# sensor.net
KiCad netlist of a schematic drawn in Altium Designer
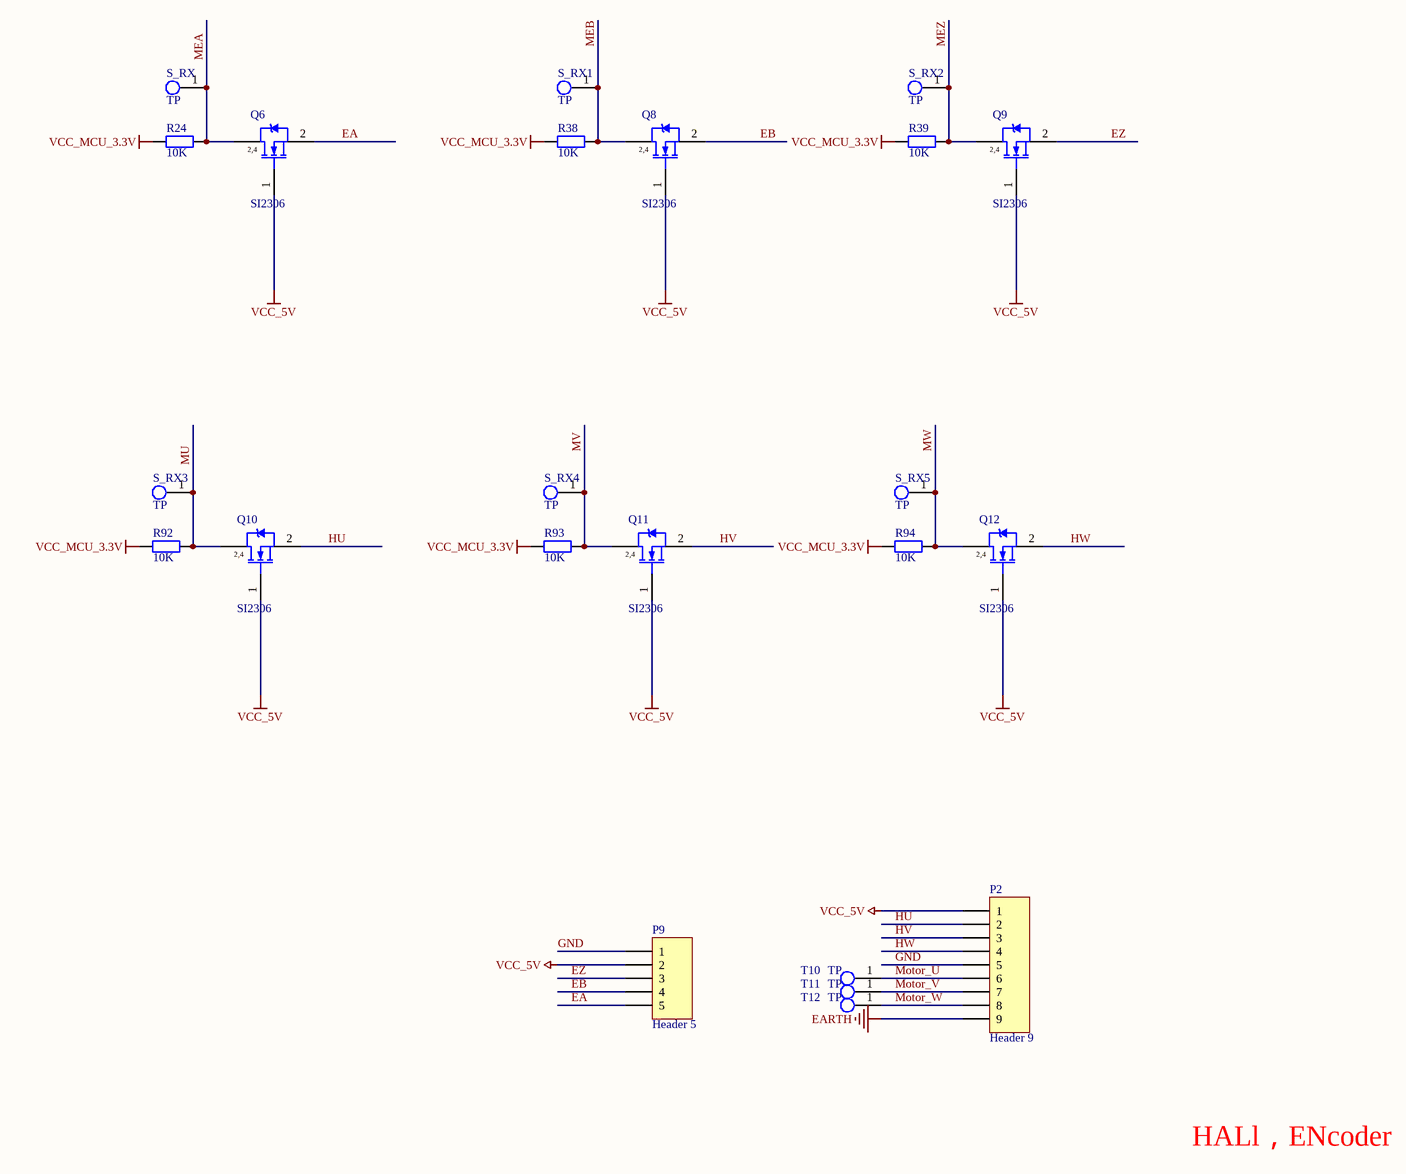
[diagram p0: sensor.SchDoc]

(export (version "E")
  (design (tool "Eeschema 10.0.6"))
  (components
    (comp (ref "P2")
      (value "Header 9")
      (footprint "XA2.5-9P")
      (description "Header, 9-Pin")
      (fields (field (name "PUBLISHER") "Altium Limited"))
      (libsource (lib "Miscellaneous Connectors") (part "Header 9"))
    )
    (comp (ref "P9")
      (value "Header 5")
      (footprint "XA2.5-5P")
      (description "Header, 5-Pin")
      (fields (field (name "PUBLISHER") "Altium Limited"))
      (libsource (lib "Miscellaneous Connectors") (part "Header 5"))
    )
    (comp (ref "Q6")
      (value "SI2306")
      (footprint "Pcblib_20110825:SOT23-3")
      (description "BUK92150-55A")
      (fields (field (name "PUBLISHER") "Altium Limited"))
      (libsource (lib "Schlib1") (part "BUK92150-55A"))
    )
    (comp (ref "Q8")
      (value "SI2306")
      (footprint "SOT23-3")
      (description "BUK92150-55A")
      (fields (field (name "PUBLISHER") "Altium Limited"))
      (libsource (lib "Schlib1") (part "BUK92150-55A"))
    )
    (comp (ref "Q9")
      (value "SI2306")
      (footprint "Pcblib_20110825:SOT23-3")
      (description "BUK92150-55A")
      (fields (field (name "PUBLISHER") "Altium Limited"))
      (libsource (lib "Schlib1") (part "BUK92150-55A"))
    )
    (comp (ref "Q10")
      (value "SI2306")
      (footprint "Pcblib_20110825:SOT23-3")
      (description "BUK92150-55A")
      (fields (field (name "PUBLISHER") "Altium Limited"))
      (libsource (lib "Schlib1") (part "BUK92150-55A"))
    )
    (comp (ref "Q11")
      (value "SI2306")
      (footprint "Pcblib_20110825:SOT23-3")
      (description "BUK92150-55A")
      (fields (field (name "PUBLISHER") "Altium Limited"))
      (libsource (lib "Schlib1") (part "BUK92150-55A"))
    )
    (comp (ref "Q12")
      (value "SI2306")
      (footprint "Pcblib_20110825:SOT23-3")
      (description "BUK92150-55A")
      (fields (field (name "PUBLISHER") "Altium Limited"))
      (libsource (lib "Schlib1") (part "BUK92150-55A"))
    )
    (comp (ref "R24")
      (value "10K")
      (footprint "Pcblib_20110825:0603R")
      (description "Resistor")
      (fields (field (name "PUBLISHER") "Altium Limited"))
      (libsource (lib "Miscellaneous Devices") (part "Res2"))
    )
    (comp (ref "R38")
      (value "10K")
      (footprint "Pcblib_20110825:0603R")
      (description "Resistor")
      (fields (field (name "PUBLISHER") "Altium Limited"))
      (libsource (lib "Miscellaneous Devices") (part "Res2"))
    )
    (comp (ref "R39")
      (value "10K")
      (footprint "Pcblib_20110825:0603R")
      (description "Resistor")
      (fields (field (name "PUBLISHER") "Altium Limited"))
      (libsource (lib "Miscellaneous Devices") (part "Res2"))
    )
    (comp (ref "R92")
      (value "10K")
      (footprint "Pcblib_20110825:0603R")
      (description "Resistor")
      (fields (field (name "PUBLISHER") "Altium Limited"))
      (libsource (lib "Miscellaneous Devices") (part "Res2"))
    )
    (comp (ref "R93")
      (value "10K")
      (footprint "Pcblib_20110825:0603R")
      (description "Resistor")
      (fields (field (name "PUBLISHER") "Altium Limited"))
      (libsource (lib "Miscellaneous Devices") (part "Res2"))
    )
    (comp (ref "R94")
      (value "10K")
      (footprint "Pcblib_20110825:0603R")
      (description "Resistor")
      (fields (field (name "PUBLISHER") "Altium Limited"))
      (libsource (lib "Miscellaneous Devices") (part "Res2"))
    )
    (comp (ref "S_RX")
      (value "TP")
      (footprint "Pcblib_20110825:TPD")
      (libsource (lib "Schlib_20110825") (part "TP"))
    )
    (comp (ref "S_RX1")
      (value "TP")
      (footprint "Pcblib_20110825:TPD")
      (libsource (lib "Schlib_20110825") (part "TP"))
    )
    (comp (ref "S_RX2")
      (value "TP")
      (footprint "Pcblib_20110825:TPD")
      (libsource (lib "Schlib_20110825") (part "TP"))
    )
    (comp (ref "S_RX3")
      (value "TP")
      (footprint "Pcblib_20110825:TPD")
      (libsource (lib "Schlib_20110825") (part "TP"))
    )
    (comp (ref "S_RX4")
      (value "TP")
      (footprint "Pcblib_20110825:TPD")
      (libsource (lib "Schlib_20110825") (part "TP"))
    )
    (comp (ref "S_RX5")
      (value "TP")
      (footprint "Pcblib_20110825:TPD")
      (libsource (lib "Schlib_20110825") (part "TP"))
    )
    (comp (ref "T10") (value "TP") (footprint "TPD") (libsource (lib "Schlib_20110825") (part "TP")))
    (comp (ref "T11") (value "TP") (footprint "TPD") (libsource (lib "Schlib_20110825") (part "TP")))
    (comp (ref "T12") (value "TP") (footprint "TPD") (libsource (lib "Schlib_20110825") (part "TP")))
  )
  (nets
    (net (code "1") (name "/EA") (class "Default")
      (node (ref "P9") (pin "5") (pinfunction "5_5") (pintype "passive"))
      (node (ref "Q6") (pin "2") (pinfunction "S_2") (pintype "passive"))
    )
    (net (code "2") (name "/EB") (class "Default")
      (node (ref "P9") (pin "4") (pinfunction "4_4") (pintype "passive"))
      (node (ref "Q8") (pin "2") (pinfunction "S_2") (pintype "passive"))
    )
    (net (code "3") (name "/EZ") (class "Default")
      (node (ref "P9") (pin "3") (pinfunction "3_3") (pintype "passive"))
      (node (ref "Q9") (pin "2") (pinfunction "S_2") (pintype "passive"))
    )
    (net (code "4") (name "/GND") (class "Default")
      (node (ref "P2") (pin "5") (pinfunction "5_5") (pintype "passive"))
      (node (ref "P9") (pin "1") (pinfunction "1_1") (pintype "passive"))
    )
    (net (code "5") (name "/HU") (class "Default")
      (node (ref "P2") (pin "2") (pinfunction "2_2") (pintype "passive"))
      (node (ref "Q10") (pin "2") (pinfunction "S_2") (pintype "passive"))
    )
    (net (code "6") (name "/HV") (class "Default")
      (node (ref "P2") (pin "3") (pinfunction "3_3") (pintype "passive"))
      (node (ref "Q11") (pin "2") (pinfunction "S_2") (pintype "passive"))
    )
    (net (code "7") (name "/HW") (class "Default")
      (node (ref "P2") (pin "4") (pinfunction "4_4") (pintype "passive"))
      (node (ref "Q12") (pin "2") (pinfunction "S_2") (pintype "passive"))
    )
    (net (code "8") (name "/MEA") (class "Default")
      (node (ref "Q6") (pin "3") (pinfunction "D_3") (pintype "passive"))
      (node (ref "R24") (pin "2") (pinfunction "2_2") (pintype "passive"))
      (node (ref "S_RX") (pin "1") (pintype "passive"))
    )
    (net (code "9") (name "/MEB") (class "Default")
      (node (ref "Q8") (pin "3") (pinfunction "D_3") (pintype "passive"))
      (node (ref "R38") (pin "2") (pinfunction "2_2") (pintype "passive"))
      (node (ref "S_RX1") (pin "1") (pintype "passive"))
    )
    (net (code "10") (name "/MEZ") (class "Default")
      (node (ref "Q9") (pin "3") (pinfunction "D_3") (pintype "passive"))
      (node (ref "R39") (pin "2") (pinfunction "2_2") (pintype "passive"))
      (node (ref "S_RX2") (pin "1") (pintype "passive"))
    )
    (net (code "11") (name "/MU") (class "Default")
      (node (ref "Q10") (pin "3") (pinfunction "D_3") (pintype "passive"))
      (node (ref "R92") (pin "2") (pinfunction "2_2") (pintype "passive"))
      (node (ref "S_RX3") (pin "1") (pintype "passive"))
    )
    (net (code "12") (name "/MV") (class "Default")
      (node (ref "Q11") (pin "3") (pinfunction "D_3") (pintype "passive"))
      (node (ref "R93") (pin "2") (pinfunction "2_2") (pintype "passive"))
      (node (ref "S_RX4") (pin "1") (pintype "passive"))
    )
    (net (code "13") (name "/MW") (class "Default")
      (node (ref "Q12") (pin "3") (pinfunction "D_3") (pintype "passive"))
      (node (ref "R94") (pin "2") (pinfunction "2_2") (pintype "passive"))
      (node (ref "S_RX5") (pin "1") (pintype "passive"))
    )
    (net (code "14") (name "/Motor_U") (class "Default")
      (node (ref "P2") (pin "6") (pinfunction "6_6") (pintype "passive"))
      (node (ref "T10") (pin "1") (pintype "passive"))
    )
    (net (code "15") (name "/Motor_V") (class "Default")
      (node (ref "P2") (pin "7") (pinfunction "7_7") (pintype "passive"))
      (node (ref "T11") (pin "1") (pintype "passive"))
    )
    (net (code "16") (name "/Motor_W") (class "Default")
      (node (ref "P2") (pin "8") (pinfunction "8_8") (pintype "passive"))
      (node (ref "T12") (pin "1") (pintype "passive"))
    )
    (net (code "17") (name "EARTH") (class "Default")
      (node (ref "P2") (pin "9") (pinfunction "9_9") (pintype "passive"))
    )
    (net (code "18") (name "VCC_5V") (class "Default")
      (node (ref "P2") (pin "1") (pinfunction "1_1") (pintype "passive"))
      (node (ref "P9") (pin "2") (pinfunction "2_2") (pintype "passive"))
      (node (ref "Q10") (pin "1") (pinfunction "G_1") (pintype "passive"))
      (node (ref "Q11") (pin "1") (pinfunction "G_1") (pintype "passive"))
      (node (ref "Q12") (pin "1") (pinfunction "G_1") (pintype "passive"))
      (node (ref "Q6") (pin "1") (pinfunction "G_1") (pintype "passive"))
      (node (ref "Q8") (pin "1") (pinfunction "G_1") (pintype "passive"))
      (node (ref "Q9") (pin "1") (pinfunction "G_1") (pintype "passive"))
    )
    (net (code "19") (name "VCC_MCU_3.3V") (class "Default")
      (node (ref "R24") (pin "1") (pinfunction "1_1") (pintype "passive"))
      (node (ref "R38") (pin "1") (pinfunction "1_1") (pintype "passive"))
      (node (ref "R39") (pin "1") (pinfunction "1_1") (pintype "passive"))
      (node (ref "R92") (pin "1") (pinfunction "1_1") (pintype "passive"))
      (node (ref "R93") (pin "1") (pinfunction "1_1") (pintype "passive"))
      (node (ref "R94") (pin "1") (pinfunction "1_1") (pintype "passive"))
    )
  )
)
